# TopLevel.net
KiCad netlist of a schematic drawn in Altium Designer
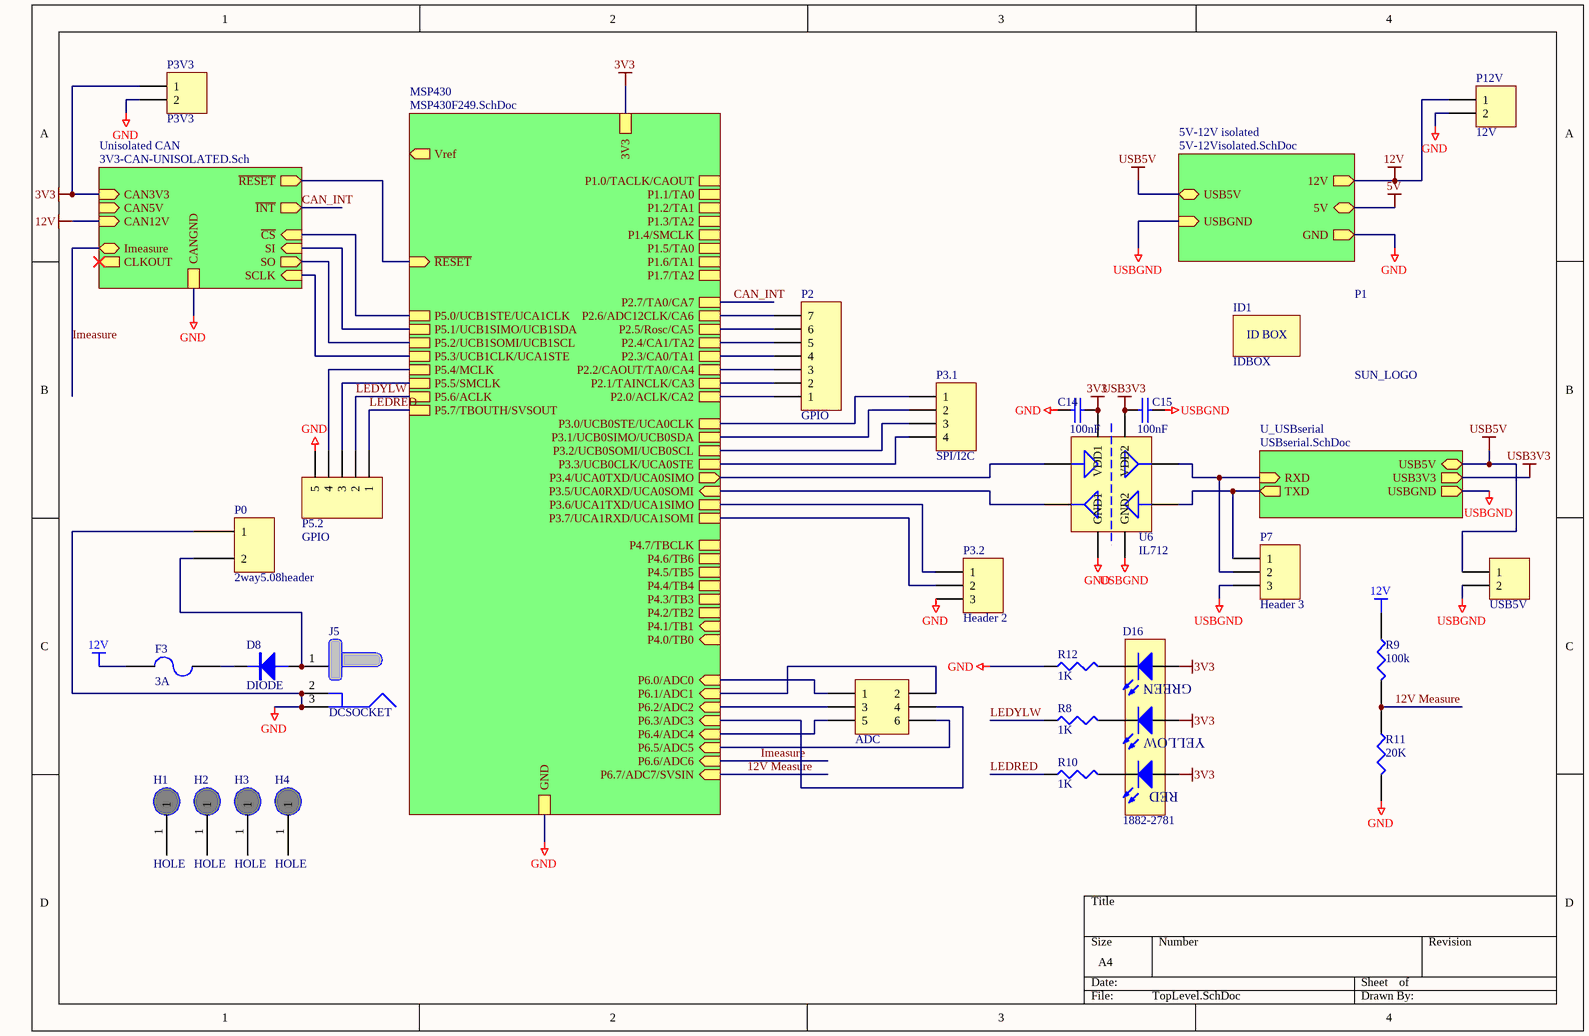
[diagram p0: TopLevel.SchDoc]

(export (version "E")
  (design (tool "Eeschema 10.0.6"))
  (components
    (comp (ref "C14")
      (value "100nF")
      (footprint "0603")
      (description "Capacitor")
      (libsource (lib "*") (part "CAP"))
    )
    (comp (ref "C15")
      (value "100nF")
      (footprint "0603")
      (description "Capacitor")
      (libsource (lib "*") (part "CAP"))
    )
    (comp (ref "D8")
      (value "DIODE")
      (footprint "Diode_1N5820")
      (description "Diode")
      (libsource (lib "RCLDQ") (part "DIODE"))
    )
    (comp (ref "D16")
      (value "1882-2781")
      (footprint "LED_TRILEVEL")
      (description "Three level LED")
      (libsource (lib "RCLDQ") (part "LED-TRILEVEL"))
    )
    (comp (ref "F3")
      (value "3A")
      (footprint "LITTELFUSE-154")
      (description "Fuse")
      (libsource (lib "*") (part "FUSE2"))
    )
    (comp (ref "H1")
      (value "HOLE")
      (footprint "M2.5")
      (description "Hole")
      (libsource (lib "Miscellaneous") (part "HOLE"))
    )
    (comp (ref "H2")
      (value "HOLE")
      (footprint "M2.5")
      (description "Hole")
      (libsource (lib "Miscellaneous") (part "HOLE"))
    )
    (comp (ref "H3")
      (value "HOLE")
      (footprint "M2.5")
      (description "Hole")
      (libsource (lib "Miscellaneous") (part "HOLE"))
    )
    (comp (ref "H4")
      (value "HOLE")
      (footprint "M2.5")
      (description "Hole")
      (libsource (lib "Miscellaneous") (part "HOLE"))
    )
    (comp (ref "ID1") (value "IDBOX") (footprint "IDBOX") (libsource (lib "Miscellaneous") (part "IDBOX")))
    (comp (ref "J5")
      (value "DCSOCKET")
      (footprint "DCSOCKET_MOD")
      (libsource (lib "Connectors") (part "DCSOCKET"))
    )
    (comp (ref "P0")
      (value "2way5.08header")
      (footprint "RightAngle2way")
      (libsource (lib "Connectors") (part "2way5.08header"))
    )
    (comp (ref "P1")
      (value "SUN_LOGO")
      (footprint "SUNSWIFTLOGO")
      (libsource (lib "Miscellaneous") (part "SUN_LOGO"))
    )
    (comp (ref "P2")
      (value "GPIO")
      (footprint "MHDR1X7")
      (description "Header, 7-Pin")
      (fields (field (name "PUBLISHER") "Altium Limited"))
      (libsource (lib "Miscellaneous Connectors") (part "MHDR1X7"))
    )
    (comp (ref "P3.1")
      (value "SPI/I2C")
      (footprint "HDR1X4")
      (description "Header, 4-Pin")
      (fields (field (name "PUBLISHER") "Altium Limited"))
      (libsource (lib "Miscellaneous Connectors") (part "Header 4"))
    )
    (comp (ref "P3.2")
      (value "Header 2")
      (footprint "HDR1X3")
      (description "Header, 3-Pin")
      (fields (field (name "PUBLISHER") "Altium Limited"))
      (libsource (lib "Miscellaneous Connectors") (part "Header 3"))
    )
    (comp (ref "P3V3")
      (value "P3V3")
      (footprint "HDR1X2")
      (description "Header, 2-Pin")
      (fields (field (name "PUBLISHER") "Altium Limited"))
      (libsource (lib "Miscellaneous Connectors") (part "Header 2"))
    )
    (comp (ref "P5.2")
      (value "GPIO")
      (footprint "HDR1X5")
      (description "Header, 5-Pin")
      (fields (field (name "PUBLISHER") "Altium Limited"))
      (libsource (lib "Miscellaneous Connectors") (part "Header 5"))
    )
    (comp (ref "P6")
      (value "ADC")
      (footprint "HDR2X3")
      (description "Header, 3-Pin, Dual row")
      (fields (field (name "PUBLISHER") "Altium Limited"))
      (libsource (lib "Miscellaneous Connectors") (part "Header 3X2"))
    )
    (comp (ref "P7")
      (value "Header 3")
      (footprint "HDR1X3")
      (description "Header, 3-Pin")
      (fields (field (name "PUBLISHER") "Altium Limited"))
      (libsource (lib "Miscellaneous Connectors") (part "Header 3"))
    )
    (comp (ref "P12V")
      (value "12V")
      (footprint "HDR1X2")
      (description "Header, 2-Pin")
      (fields (field (name "PUBLISHER") "Altium Limited"))
      (libsource (lib "Miscellaneous Connectors") (part "Header 2"))
    )
    (comp (ref "PUSB5V")
      (value "USB5V")
      (footprint "HDR1X2")
      (description "Header, 2-Pin")
      (fields (field (name "PUBLISHER") "Altium Limited"))
      (libsource (lib "Miscellaneous Connectors") (part "Header 2"))
    )
    (comp (ref "R8")
      (value "1K")
      (footprint "0603")
      (description "Resistor")
      (libsource (lib "RCLDQ") (part "RES1"))
    )
    (comp (ref "R9") (value "100k") (footprint "1206") (libsource (lib "*") (part "RES1")))
    (comp (ref "R10")
      (value "1K")
      (footprint "0603")
      (description "Resistor")
      (libsource (lib "RCLDQ") (part "RES1"))
    )
    (comp (ref "R11") (value "20K") (footprint "1206") (libsource (lib "*") (part "RES1")))
    (comp (ref "R12")
      (value "1K")
      (footprint "0603")
      (description "Resistor")
      (libsource (lib "RCLDQ") (part "RES1"))
    )
    (comp (ref "U6")
      (value "IL712")
      (footprint "SO8")
      (description "IL712 Optical Isolator")
      (libsource (lib "Optocouplers") (part "IL712"))
    )
  )
  (nets
    (net (code "1") (name "/12V Measure") (class "Default")
      (node (ref "R11") (pin "1") (pinfunction "1_1") (pintype "passive"))
      (node (ref "R9") (pin "2") (pinfunction "2_2") (pintype "passive"))
    )
    (net (code "7") (name "/LEDRED") (class "Default")
      (node (ref "P5.2") (pin "1") (pinfunction "1_1") (pintype "passive"))
      (node (ref "R10") (pin "1") (pinfunction "1_1") (pintype "passive"))
    )
    (net (code "8") (name "/LEDYLW") (class "Default")
      (node (ref "P5.2") (pin "2") (pinfunction "2_2") (pintype "passive"))
      (node (ref "R8") (pin "1") (pinfunction "1_1") (pintype "passive"))
    )
    (net (code "17") (name "/P2.0{slash}ACLK{slash}CA2") (class "Default")
      (node (ref "P2") (pin "1") (pinfunction "1_1") (pintype "passive"))
    )
    (net (code "18") (name "/P2.1{slash}TAINCLK{slash}CA3") (class "Default")
      (node (ref "P2") (pin "2") (pinfunction "2_2") (pintype "passive"))
    )
    (net (code "19") (name "/P2.2{slash}CAOUT{slash}TA0{slash}CA4") (class "Default")
      (node (ref "P2") (pin "3") (pinfunction "3_3") (pintype "passive"))
    )
    (net (code "20") (name "/P2.3{slash}CA0{slash}TA1") (class "Default")
      (node (ref "P2") (pin "4") (pinfunction "4_4") (pintype "passive"))
    )
    (net (code "21") (name "/P2.4{slash}CA1{slash}TA2") (class "Default")
      (node (ref "P2") (pin "5") (pinfunction "5_5") (pintype "passive"))
    )
    (net (code "22") (name "/P2.5{slash}Rosc{slash}CA5") (class "Default")
      (node (ref "P2") (pin "6") (pinfunction "6_6") (pintype "passive"))
    )
    (net (code "23") (name "/P2.6{slash}ADC12CLK{slash}CA6") (class "Default")
      (node (ref "P2") (pin "7") (pinfunction "7_7") (pintype "passive"))
    )
    (net (code "24") (name "/P3.0{slash}UCB0STE{slash}UCA0CLK") (class "Default")
      (node (ref "P3.1") (pin "1") (pinfunction "1_1") (pintype "passive"))
    )
    (net (code "25") (name "/P3.1{slash}UCB0SIMO{slash}UCB0SDA") (class "Default")
      (node (ref "P3.1") (pin "2") (pinfunction "2_2") (pintype "passive"))
    )
    (net (code "26") (name "/P3.2{slash}UCB0SOMI{slash}UCB0SCL") (class "Default")
      (node (ref "P3.1") (pin "3") (pinfunction "3_3") (pintype "passive"))
    )
    (net (code "27") (name "/P3.3{slash}UCB0CLK{slash}UCA0STE") (class "Default")
      (node (ref "P3.1") (pin "4") (pinfunction "4_4") (pintype "passive"))
    )
    (net (code "28") (name "/P3.4{slash}UCA0TXD{slash}UCA0SIMO") (class "Default")
      (node (ref "U6") (pin "2") (pinfunction "IN1_2") (pintype "passive"))
    )
    (net (code "29") (name "/P3.5{slash}UCA0RXD{slash}UCA0SOMI") (class "Default")
      (node (ref "U6") (pin "3") (pinfunction "OUT2_3") (pintype "passive"))
    )
    (net (code "30") (name "/P3.6{slash}UCA1TXD{slash}UCA1SIMO") (class "Default")
      (node (ref "P3.2") (pin "1") (pinfunction "1_1") (pintype "passive"))
    )
    (net (code "31") (name "/P3.7{slash}UCA1RXD{slash}UCA1SOMI") (class "Default")
      (node (ref "P3.2") (pin "2") (pinfunction "2_2") (pintype "passive"))
    )
    (net (code "42") (name "/P5.4{slash}MCLK") (class "Default")
      (node (ref "P5.2") (pin "4") (pinfunction "4_4") (pintype "passive"))
    )
    (net (code "43") (name "/P5.5{slash}SMCLK") (class "Default")
      (node (ref "P5.2") (pin "3") (pinfunction "3_3") (pintype "passive"))
    )
    (net (code "44") (name "/P6.0{slash}ADC0") (class "Default")
      (node (ref "P6") (pin "1") (pinfunction "1_1") (pintype "passive"))
    )
    (net (code "45") (name "/P6.1{slash}ADC1") (class "Default")
      (node (ref "P6") (pin "2") (pinfunction "2_2") (pintype "passive"))
    )
    (net (code "46") (name "/P6.2{slash}ADC2") (class "Default")
      (node (ref "P6") (pin "3") (pinfunction "3_3") (pintype "passive"))
    )
    (net (code "47") (name "/P6.3{slash}ADC3") (class "Default")
      (node (ref "P6") (pin "4") (pinfunction "4_4") (pintype "passive"))
    )
    (net (code "48") (name "/P6.4{slash}ADC4") (class "Default")
      (node (ref "P6") (pin "5") (pinfunction "5_5") (pintype "passive"))
    )
    (net (code "49") (name "/P6.5{slash}ADC5") (class "Default")
      (node (ref "P6") (pin "6") (pinfunction "6_6") (pintype "passive"))
    )
    (net (code "51") (name "/RXD") (class "Default")
      (node (ref "P7") (pin "2") (pinfunction "2_2") (pintype "passive"))
      (node (ref "U6") (pin "7") (pinfunction "OUT1_7") (pintype "passive"))
    )
    (net (code "53") (name "/TXD") (class "Default")
      (node (ref "P7") (pin "1") (pinfunction "1_1") (pintype "passive"))
      (node (ref "U6") (pin "6") (pinfunction "IN2_6") (pintype "passive"))
    )
    (net (code "55") (name "3V3") (class "Default")
      (node (ref "C14") (pin "2") (pinfunction "2_2") (pintype "passive"))
      (node (ref "D16") (pin "4") (pinfunction "A_4") (pintype "passive"))
      (node (ref "D16") (pin "5") (pinfunction "A_5") (pintype "passive"))
      (node (ref "D16") (pin "6") (pinfunction "A_6") (pintype "passive"))
      (node (ref "P3V3") (pin "1") (pinfunction "1_1") (pintype "passive"))
      (node (ref "U6") (pin "1") (pinfunction "VDD1_1") (pintype "passive"))
    )
    (net (code "57") (name "12V") (class "Default")
      (node (ref "F3") (pin "1") (pinfunction "1_1") (pintype "passive"))
      (node (ref "P12V") (pin "1") (pinfunction "1_1") (pintype "passive"))
      (node (ref "R9") (pin "1") (pinfunction "1_1") (pintype "passive"))
    )
    (net (code "58") (name "GND") (class "Default")
      (node (ref "C14") (pin "1") (pinfunction "1_1") (pintype "passive"))
      (node (ref "J5") (pin "2") (pinfunction "2_2") (pintype "passive"))
      (node (ref "J5") (pin "3") (pinfunction "3_3") (pintype "passive"))
      (node (ref "P0") (pin "1") (pinfunction "1_1") (pintype "passive"))
      (node (ref "P12V") (pin "2") (pinfunction "2_2") (pintype "passive"))
      (node (ref "P3.2") (pin "3") (pinfunction "3_3") (pintype "passive"))
      (node (ref "P3V3") (pin "2") (pinfunction "2_2") (pintype "passive"))
      (node (ref "P5.2") (pin "5") (pinfunction "5_5") (pintype "passive"))
      (node (ref "R11") (pin "2") (pinfunction "2_2") (pintype "passive"))
      (node (ref "R12") (pin "1") (pinfunction "1_1") (pintype "passive"))
      (node (ref "U6") (pin "4") (pinfunction "GND1_4") (pintype "passive"))
    )
    (net (code "59") (name "Net-(D8-PadA)") (class "Default")
      (node (ref "D8") (pin "A") (pinfunction "A_A") (pintype "passive"))
      (node (ref "J5") (pin "1") (pinfunction "1_1") (pintype "passive"))
      (node (ref "P0") (pin "2") (pinfunction "2_2") (pintype "passive"))
    )
    (net (code "60") (name "Net-(D8-PadK)") (class "Default")
      (node (ref "D8") (pin "K") (pinfunction "K_K") (pintype "passive"))
      (node (ref "F3") (pin "2") (pinfunction "2_2") (pintype "passive"))
    )
    (net (code "61") (name "Net-(D16-K-Pad1)") (class "Default")
      (node (ref "D16") (pin "1") (pinfunction "K_1") (pintype "passive"))
      (node (ref "R12") (pin "2") (pinfunction "2_2") (pintype "passive"))
    )
    (net (code "62") (name "Net-(D16-K-Pad2)") (class "Default")
      (node (ref "D16") (pin "2") (pinfunction "K_2") (pintype "passive"))
      (node (ref "R8") (pin "2") (pinfunction "2_2") (pintype "passive"))
    )
    (net (code "63") (name "Net-(D16-K-Pad3)") (class "Default")
      (node (ref "D16") (pin "3") (pinfunction "K_3") (pintype "passive"))
      (node (ref "R10") (pin "2") (pinfunction "2_2") (pintype "passive"))
    )
    (net (code "64") (name "USB3V3") (class "Default")
      (node (ref "C15") (pin "1") (pinfunction "1_1") (pintype "passive"))
      (node (ref "U6") (pin "8") (pinfunction "VDD2_8") (pintype "passive"))
    )
    (net (code "65") (name "USB5V") (class "Default")
      (node (ref "PUSB5V") (pin "1") (pinfunction "1_1") (pintype "passive"))
    )
    (net (code "66") (name "USBGND") (class "Default")
      (node (ref "C15") (pin "2") (pinfunction "2_2") (pintype "passive"))
      (node (ref "P7") (pin "3") (pinfunction "3_3") (pintype "passive"))
      (node (ref "PUSB5V") (pin "2") (pinfunction "2_2") (pintype "passive"))
      (node (ref "U6") (pin "5") (pinfunction "GND2_5") (pintype "passive"))
    )
    (net (code "67") (name "unconnected-(H1-Pad1)") (class "Default")
      (node (ref "H1") (pin "1") (pinfunction "1_1") (pintype "passive"))
    )
    (net (code "68") (name "unconnected-(H2-Pad1)") (class "Default")
      (node (ref "H2") (pin "1") (pinfunction "1_1") (pintype "passive"))
    )
    (net (code "69") (name "unconnected-(H3-Pad1)") (class "Default")
      (node (ref "H3") (pin "1") (pinfunction "1_1") (pintype "passive"))
    )
    (net (code "70") (name "unconnected-(H4-Pad1)") (class "Default")
      (node (ref "H4") (pin "1") (pinfunction "1_1") (pintype "passive"))
    )
  )
)
